# Leds_and_Buttons.net
KiCad netlist of a schematic drawn in Altium Designer
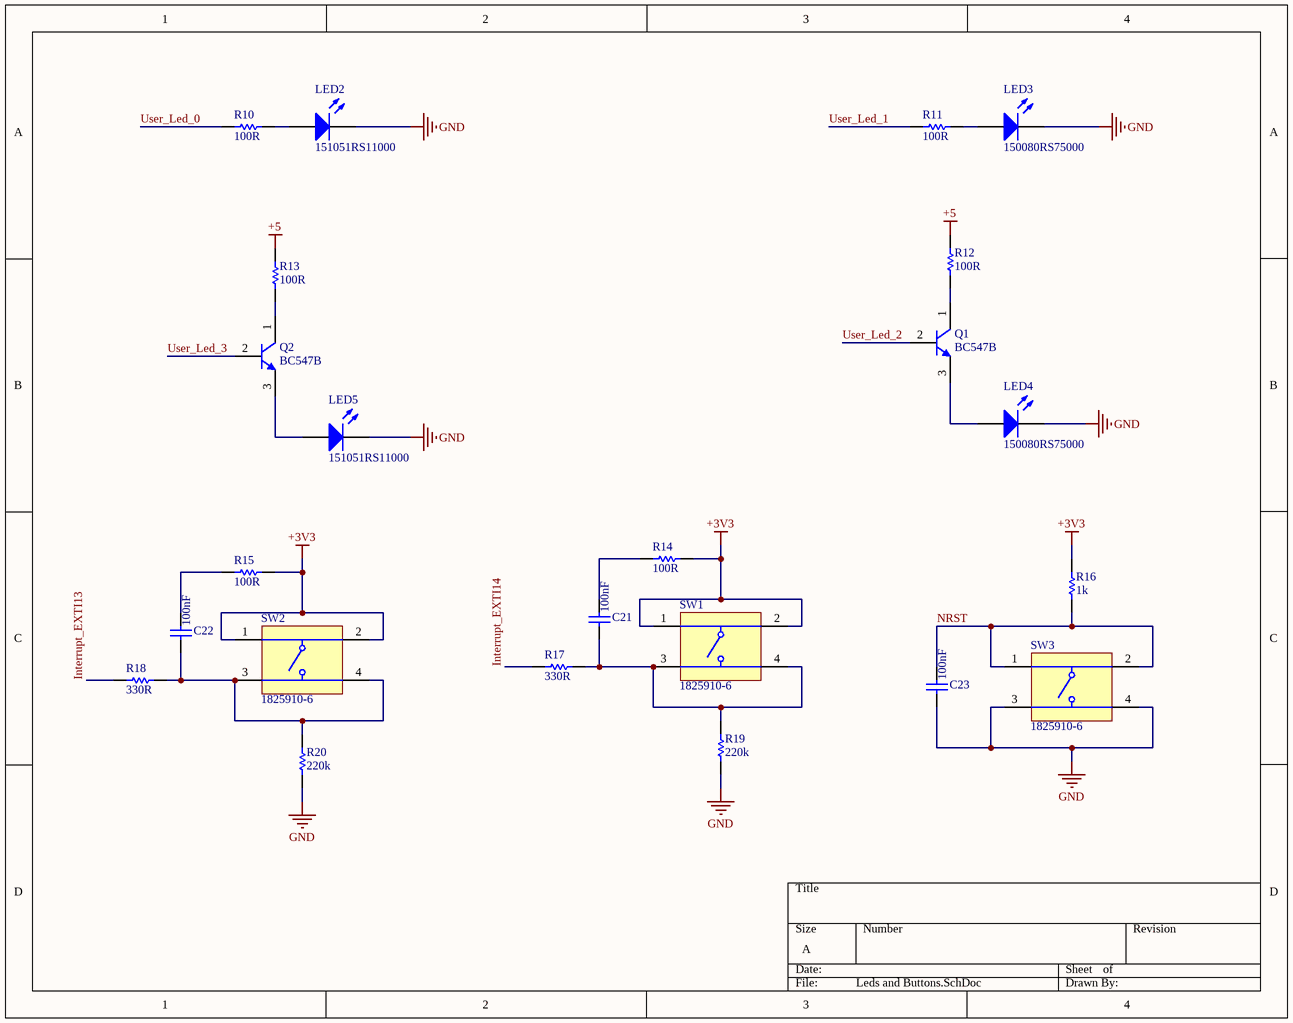
[diagram p0: Leds and Buttons.SchDoc]

(export (version "E")
  (design (tool "Eeschema 10.0.6"))
  (components
    (comp (ref "C21")
      (value "100nF")
      (footprint "CAPC2013X135X45LL10T25")
      (fields (field (name "MANUFACTURER") "Murata") (field (name "PART NUMBER") "GRM21BR71H105KA12L"))
      (libsource (lib "Altium Content Vault") (part "CAP"))
    )
    (comp (ref "C22")
      (value "100nF")
      (footprint "CAPC2013X135X45LL10T25")
      (fields (field (name "MANUFACTURER") "Murata") (field (name "PART NUMBER") "GRM21BR71H105KA12L"))
      (libsource (lib "Altium Content Vault") (part "CAP"))
    )
    (comp (ref "C23")
      (value "100nF")
      (footprint "CAPC2013X135X45LL10T25")
      (fields (field (name "MANUFACTURER") "Murata") (field (name "PART NUMBER") "GRM21BR71H105KA12L"))
      (libsource (lib "Altium Content Vault") (part "CAP"))
    )
    (comp (ref "LED2")
      (value "151051RS11000")
      (footprint "Type 5mm")
      (description "THT LED round mono-color color lens, WL-TMRW, Red")
      (fields (field (name "MANUFACTURER") "Wuerth Elektronik"))
      (libsource (lib "Altium Content Vault") (part "WE-LED_K1A2-2"))
    )
    (comp (ref "LED3")
      (value "150080RS75000")
      (footprint "0805_A")
      (description "SMD mono-color Chip LED, WL-SMCW, Red")
      (fields (field (name "MANUFACTURER") "Wuerth Elektronik"))
      (libsource (lib "Altium Content Vault") (part "WE-LED_K1A2-2"))
    )
    (comp (ref "LED4")
      (value "150080RS75000")
      (footprint "0805_A")
      (description "SMD mono-color Chip LED, WL-SMCW, Red")
      (fields (field (name "MANUFACTURER") "Wuerth Elektronik"))
      (libsource (lib "Altium Content Vault") (part "WE-LED_K1A2-2"))
    )
    (comp (ref "LED5")
      (value "151051RS11000")
      (footprint "Type 5mm")
      (description "THT LED round mono-color color lens, WL-TMRW, Red")
      (fields (field (name "MANUFACTURER") "Wuerth Elektronik"))
      (libsource (lib "Altium Content Vault") (part "WE-LED_K1A2-2"))
    )
    (comp (ref "Q1")
      (value "BC547B")
      (footprint "ONSC-TO-92-3-29-11")
      (description "Amplifier Transistor, NPN Silicon, 3-Pin TO-92, Bulk Box")
      (fields (field (name "MANUFACTURER") "On Semiconductor"))
      (libsource (lib "Altium Content Vault") (part "ONSC-NPN-C1B2E3-3"))
    )
    (comp (ref "Q2")
      (value "BC547B")
      (footprint "ONSC-TO-92-3-29-11")
      (description "Amplifier Transistor, NPN Silicon, 3-Pin TO-92, Bulk Box")
      (fields (field (name "MANUFACTURER") "On Semiconductor"))
      (libsource (lib "Altium Content Vault") (part "ONSC-NPN-C1B2E3-3"))
    )
    (comp (ref "R10")
      (value "100R")
      (footprint "RESC2013X70X40NL20T20")
      (fields (field (name "PART NUMBER") "ERJ6ENF47R0V") (field (name "MANUFACTURER") "Panasonic"))
      (libsource (lib "Altium Content Vault") (part "RES"))
    )
    (comp (ref "R11")
      (value "100R")
      (footprint "RESC2013X70X40NL20T20")
      (fields (field (name "PART NUMBER") "ERJ6ENF47R0V") (field (name "MANUFACTURER") "Panasonic"))
      (libsource (lib "Altium Content Vault") (part "RES"))
    )
    (comp (ref "R12")
      (value "100R")
      (footprint "RESC2013X70X40NL20T20")
      (fields (field (name "PART NUMBER") "ERJ6ENF47R0V") (field (name "MANUFACTURER") "Panasonic"))
      (libsource (lib "Altium Content Vault") (part "RES"))
    )
    (comp (ref "R13")
      (value "100R")
      (footprint "RESC2013X70X40NL20T20")
      (fields (field (name "PART NUMBER") "ERJ6ENF47R0V") (field (name "MANUFACTURER") "Panasonic"))
      (libsource (lib "Altium Content Vault") (part "RES"))
    )
    (comp (ref "R14")
      (value "100R")
      (footprint "RESC2013X70X40NL20T20")
      (fields (field (name "PART NUMBER") "ERJ6ENF47R0V") (field (name "MANUFACTURER") "Panasonic"))
      (libsource (lib "Altium Content Vault") (part "RES"))
    )
    (comp (ref "R15")
      (value "100R")
      (footprint "RESC2013X70X40NL20T20")
      (fields (field (name "PART NUMBER") "ERJ6ENF47R0V") (field (name "MANUFACTURER") "Panasonic"))
      (libsource (lib "Altium Content Vault") (part "RES"))
    )
    (comp (ref "R16")
      (value "1k")
      (footprint "RESC2013X70X40NL20T20")
      (fields (field (name "PART NUMBER") "ERJ6ENF47R0V") (field (name "MANUFACTURER") "Panasonic"))
      (libsource (lib "Altium Content Vault") (part "RES"))
    )
    (comp (ref "R17")
      (value "330R")
      (footprint "RESC2013X70X40NL20T20")
      (fields (field (name "PART NUMBER") "ERJ6ENF47R0V") (field (name "MANUFACTURER") "Panasonic"))
      (libsource (lib "Altium Content Vault") (part "RES"))
    )
    (comp (ref "R18")
      (value "330R")
      (footprint "RESC2013X70X40NL20T20")
      (fields (field (name "PART NUMBER") "ERJ6ENF47R0V") (field (name "MANUFACTURER") "Panasonic"))
      (libsource (lib "Altium Content Vault") (part "RES"))
    )
    (comp (ref "R19")
      (value "220k")
      (footprint "RESC2013X70X40NL20T20")
      (fields (field (name "PART NUMBER") "ERJ6ENF47R0V") (field (name "MANUFACTURER") "Panasonic"))
      (libsource (lib "Altium Content Vault") (part "RES"))
    )
    (comp (ref "R20")
      (value "220k")
      (footprint "RESC2013X70X40NL20T20")
      (fields (field (name "PART NUMBER") "ERJ6ENF47R0V") (field (name "MANUFACTURER") "Panasonic"))
      (libsource (lib "Altium Content Vault") (part "RES"))
    )
    (comp (ref "SW1")
      (value "1825910-6")
      (footprint "TECO-1825910-6_V")
      (description "Tact Switch, SPST-NO, 0.05 A, -35 to 85 degC, 4-Pin THD, RoHS, Bulk")
      (fields (field (name "MANUFACTURER") "TE Connectivity"))
      (libsource (lib "Altium Content Vault") (part "SW-SPST-4_A"))
    )
    (comp (ref "SW2")
      (value "1825910-6")
      (footprint "TECO-1825910-6_V")
      (description "Tact Switch, SPST-NO, 0.05 A, -35 to 85 degC, 4-Pin THD, RoHS, Bulk")
      (fields (field (name "MANUFACTURER") "TE Connectivity"))
      (libsource (lib "Altium Content Vault") (part "SW-SPST-4_A"))
    )
    (comp (ref "SW3")
      (value "1825910-6")
      (footprint "TECO-1825910-6_V")
      (description "Tact Switch, SPST-NO, 0.05 A, -35 to 85 degC, 4-Pin THD, RoHS, Bulk")
      (fields (field (name "MANUFACTURER") "TE Connectivity"))
      (libsource (lib "Altium Content Vault") (part "SW-SPST-4_A"))
    )
  )
  (nets
    (net (code "1") (name "+3V3") (class "Default")
      (node (ref "R14") (pin "2") (pinfunction "2_2") (pintype "passive"))
      (node (ref "R15") (pin "2") (pinfunction "2_2") (pintype "passive"))
      (node (ref "R16") (pin "2") (pinfunction "2_2") (pintype "passive"))
      (node (ref "SW1") (pin "1") (pinfunction "1_1") (pintype "passive"))
      (node (ref "SW1") (pin "2") (pinfunction "2_2") (pintype "passive"))
      (node (ref "SW2") (pin "1") (pinfunction "1_1") (pintype "passive"))
      (node (ref "SW2") (pin "2") (pinfunction "2_2") (pintype "passive"))
    )
    (net (code "2") (name "+5") (class "Default")
      (node (ref "R12") (pin "1") (pinfunction "1_1") (pintype "passive"))
      (node (ref "R13") (pin "1") (pinfunction "1_1") (pintype "passive"))
    )
    (net (code "3") (name "/Interrupt_EXTI13") (class "Default")
      (node (ref "R18") (pin "1") (pinfunction "1_1") (pintype "passive"))
    )
    (net (code "4") (name "/Interrupt_EXTI14") (class "Default")
      (node (ref "R17") (pin "1") (pinfunction "1_1") (pintype "passive"))
    )
    (net (code "5") (name "/NRST") (class "Default")
      (node (ref "C23") (pin "2") (pinfunction "2_2") (pintype "passive"))
      (node (ref "R16") (pin "1") (pinfunction "1_1") (pintype "passive"))
      (node (ref "SW3") (pin "1") (pinfunction "1_1") (pintype "passive"))
      (node (ref "SW3") (pin "2") (pinfunction "2_2") (pintype "passive"))
    )
    (net (code "6") (name "/User_Led_0") (class "Default")
      (node (ref "R10") (pin "1") (pinfunction "1_1") (pintype "passive"))
    )
    (net (code "7") (name "/User_Led_1") (class "Default")
      (node (ref "R11") (pin "1") (pinfunction "1_1") (pintype "passive"))
    )
    (net (code "8") (name "/User_Led_2") (class "Default")
      (node (ref "Q1") (pin "2") (pinfunction "B_2") (pintype "passive"))
    )
    (net (code "9") (name "/User_Led_3") (class "Default")
      (node (ref "Q2") (pin "2") (pinfunction "B_2") (pintype "passive"))
    )
    (net (code "10") (name "GND") (class "Default")
      (node (ref "C23") (pin "1") (pinfunction "1_1") (pintype "passive"))
      (node (ref "LED2") (pin "1") (pinfunction "K_1") (pintype "passive"))
      (node (ref "LED3") (pin "1") (pinfunction "K_1") (pintype "passive"))
      (node (ref "LED4") (pin "1") (pinfunction "K_1") (pintype "passive"))
      (node (ref "LED5") (pin "1") (pinfunction "K_1") (pintype "passive"))
      (node (ref "R19") (pin "1") (pinfunction "1_1") (pintype "passive"))
      (node (ref "R20") (pin "1") (pinfunction "1_1") (pintype "passive"))
      (node (ref "SW3") (pin "3") (pinfunction "3_3") (pintype "passive"))
      (node (ref "SW3") (pin "4") (pinfunction "4_4") (pintype "passive"))
    )
    (net (code "11") (name "Net-(C21-Pad1)") (class "Default")
      (node (ref "C21") (pin "1") (pinfunction "1_1") (pintype "passive"))
      (node (ref "R17") (pin "2") (pinfunction "2_2") (pintype "passive"))
      (node (ref "R19") (pin "2") (pinfunction "2_2") (pintype "passive"))
      (node (ref "SW1") (pin "3") (pinfunction "3_3") (pintype "passive"))
      (node (ref "SW1") (pin "4") (pinfunction "4_4") (pintype "passive"))
    )
    (net (code "12") (name "Net-(C21-Pad2)") (class "Default")
      (node (ref "C21") (pin "2") (pinfunction "2_2") (pintype "passive"))
      (node (ref "R14") (pin "1") (pinfunction "1_1") (pintype "passive"))
    )
    (net (code "13") (name "Net-(C22-Pad1)") (class "Default")
      (node (ref "C22") (pin "1") (pinfunction "1_1") (pintype "passive"))
      (node (ref "R18") (pin "2") (pinfunction "2_2") (pintype "passive"))
      (node (ref "R20") (pin "2") (pinfunction "2_2") (pintype "passive"))
      (node (ref "SW2") (pin "3") (pinfunction "3_3") (pintype "passive"))
      (node (ref "SW2") (pin "4") (pinfunction "4_4") (pintype "passive"))
    )
    (net (code "14") (name "Net-(C22-Pad2)") (class "Default")
      (node (ref "C22") (pin "2") (pinfunction "2_2") (pintype "passive"))
      (node (ref "R15") (pin "1") (pinfunction "1_1") (pintype "passive"))
    )
    (net (code "15") (name "Net-(LED2-A)") (class "Default")
      (node (ref "LED2") (pin "2") (pinfunction "A_2") (pintype "passive"))
      (node (ref "R10") (pin "2") (pinfunction "2_2") (pintype "passive"))
    )
    (net (code "16") (name "Net-(LED3-A)") (class "Default")
      (node (ref "LED3") (pin "2") (pinfunction "A_2") (pintype "passive"))
      (node (ref "R11") (pin "2") (pinfunction "2_2") (pintype "passive"))
    )
    (net (code "17") (name "Net-(LED4-A)") (class "Default")
      (node (ref "LED4") (pin "2") (pinfunction "A_2") (pintype "passive"))
      (node (ref "Q1") (pin "3") (pinfunction "E_3") (pintype "passive"))
    )
    (net (code "18") (name "Net-(LED5-A)") (class "Default")
      (node (ref "LED5") (pin "2") (pinfunction "A_2") (pintype "passive"))
      (node (ref "Q2") (pin "3") (pinfunction "E_3") (pintype "passive"))
    )
    (net (code "19") (name "Net-(Q1-C)") (class "Default")
      (node (ref "Q1") (pin "1") (pinfunction "C_1") (pintype "passive"))
      (node (ref "R12") (pin "2") (pinfunction "2_2") (pintype "passive"))
    )
    (net (code "20") (name "Net-(Q2-C)") (class "Default")
      (node (ref "Q2") (pin "1") (pinfunction "C_1") (pintype "passive"))
      (node (ref "R13") (pin "2") (pinfunction "2_2") (pintype "passive"))
    )
  )
)
